# SCH_Business-Card_2024-06-06.net
KiCad netlist of a schematic drawn in EasyEDA
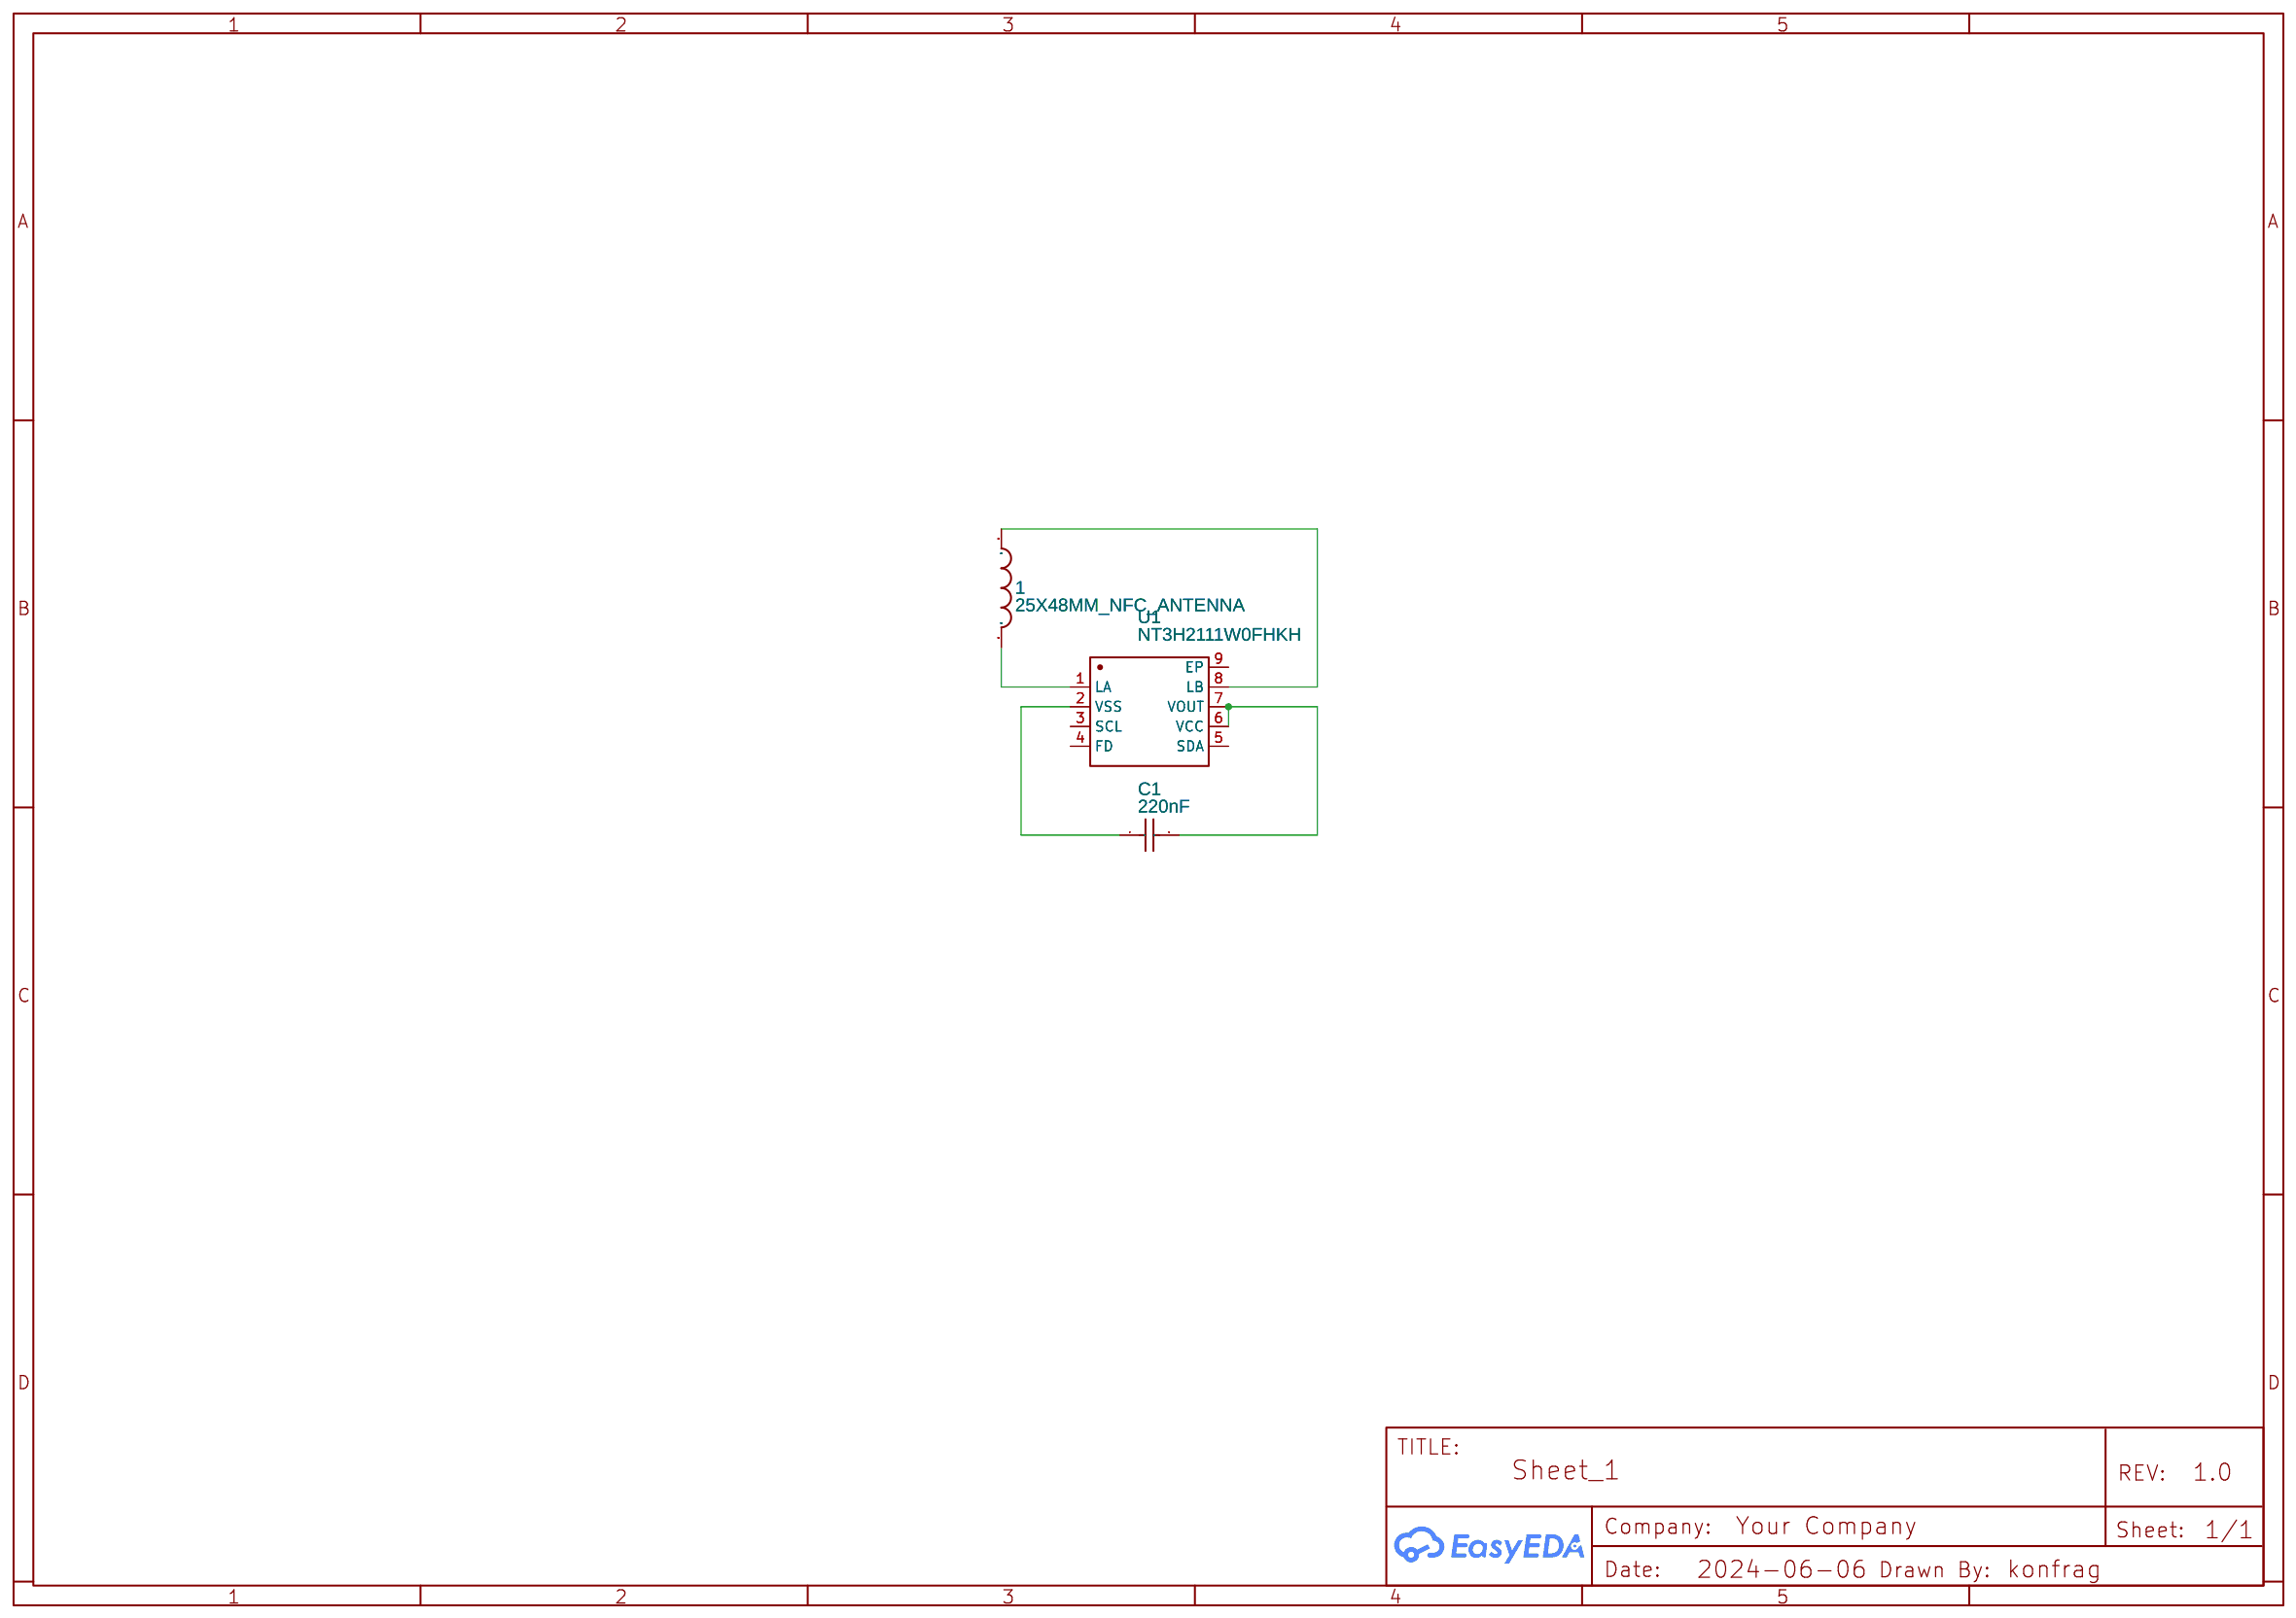
[diagram p0: schematic sheet]

(export (version "E")
  (design (tool "Eeschema 10.0.6"))
  (components
    (comp (ref "1") (value "25X48MM_NFC_ANTENNA") (libsource (lib "") (part "25X48MM_NFC_ANTENNA")))
    (comp (ref "C1")
      (value "220nF")
      (fields
        (field (name "Manufacturer Part") "CL10B224KA8NNNC")
        (field (name "Manufacturer") "SAMSUNG(三星)")
      )
      (libsource (lib "") (part "CL10B224KA8NNNC"))
    )
    (comp (ref "U1")
      (value "NT3H2111W0FHKH")
      (fields (field (name "Manufacturer") "NXP(恩智浦)"))
      (libsource (lib "") (part "NT3H2111W0FHKH"))
    )
  )
  (nets
    (net (code "1") (name "Net-(U1-LA)") (class "Default")
      (node (ref "1") (pin "P$2") (pinfunction "P$2_P$2") (pintype "bidirectional"))
      (node (ref "U1") (pin "1") (pinfunction "LA_1") (pintype "unspecified"))
    )
    (net (code "2") (name "Net-(U1-LB)") (class "Default")
      (node (ref "1") (pin "P$1") (pinfunction "P$1_P$1") (pintype "bidirectional"))
      (node (ref "U1") (pin "8") (pinfunction "LB_8") (pintype "unspecified"))
    )
    (net (code "3") (name "Net-(U1-VCC)") (class "Default")
      (node (ref "C1") (pin "2") (pinfunction "2_2") (pintype "input"))
      (node (ref "U1") (pin "6") (pinfunction "VCC_6") (pintype "unspecified"))
      (node (ref "U1") (pin "7") (pinfunction "VOUT_7") (pintype "unspecified"))
    )
    (net (code "4") (name "Net-(U1-VSS)") (class "Default")
      (node (ref "C1") (pin "1") (pinfunction "1_1") (pintype "input"))
      (node (ref "U1") (pin "2") (pinfunction "VSS_2") (pintype "unspecified"))
    )
    (net (code "5") (name "unconnected-(U1-EP-Pad9)") (class "Default")
      (node (ref "U1") (pin "9") (pinfunction "EP_9") (pintype "unspecified"))
    )
    (net (code "6") (name "unconnected-(U1-FD-Pad4)") (class "Default")
      (node (ref "U1") (pin "4") (pinfunction "FD_4") (pintype "unspecified"))
    )
    (net (code "7") (name "unconnected-(U1-SCL-Pad3)") (class "Default")
      (node (ref "U1") (pin "3") (pinfunction "SCL_3") (pintype "unspecified"))
    )
    (net (code "8") (name "unconnected-(U1-SDA-Pad5)") (class "Default")
      (node (ref "U1") (pin "5") (pinfunction "SDA_5") (pintype "unspecified"))
    )
  )
)
